# ADF7021_Transceiver.net
KiCad netlist of a schematic drawn in Altium Designer
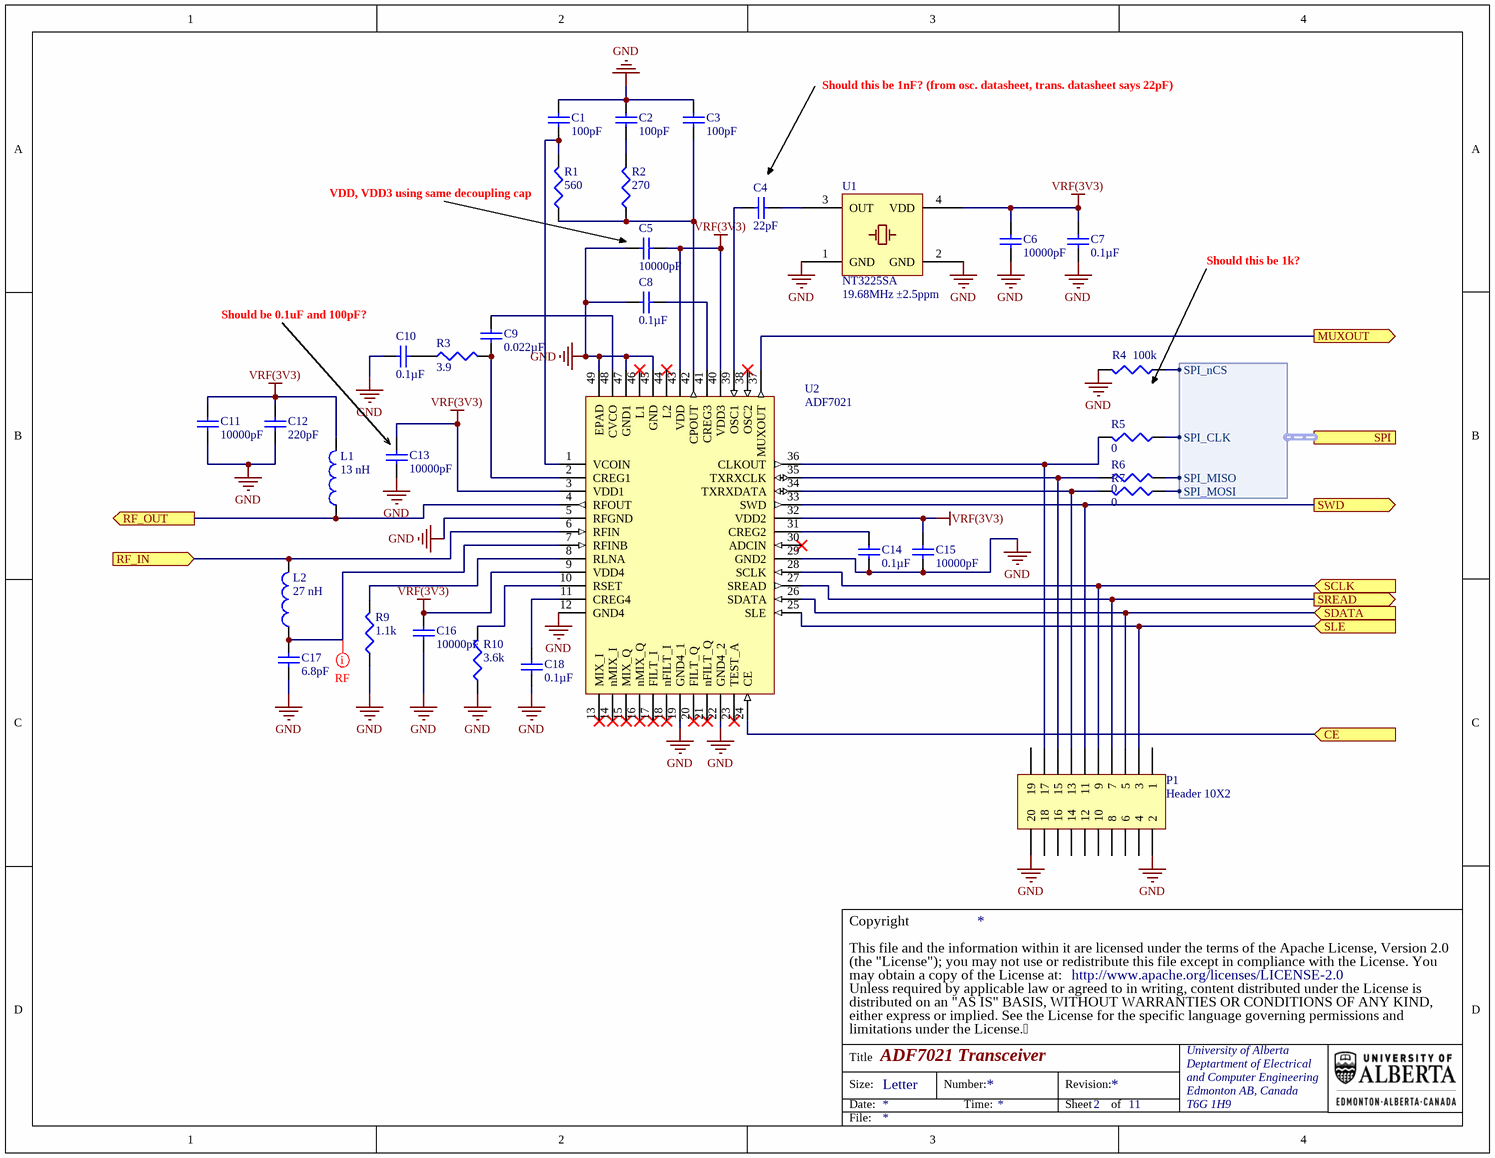
[diagram p0: ADF7021 Transceiver.SchDoc]

(export (version "E")
  (design (tool "Eeschema 10.0.6"))
  (components
    (comp (ref "C1")
      (value "100pF")
      (footprint "TDK-CGA2B")
      (description "CAP CER 100PF 100V C0G 0402")
      (fields
        (field (name "PART NUMBER") "PC-TDK-01226")
        (field (name "MANUFACTURER PART NUMBER") "CGA2B2C0G2A101J050BA")
        (field (name "PUBLISHER") "AlbertaSat")
      )
      (libsource (lib "Database") (part "Cap"))
    )
    (comp (ref "C2")
      (value "100pF")
      (footprint "TDK-CGA2B")
      (description "CAP CER 100PF 100V C0G 0402")
      (fields
        (field (name "PART NUMBER") "PC-TDK-01226")
        (field (name "MANUFACTURER PART NUMBER") "CGA2B2C0G2A101J050BA")
        (field (name "PUBLISHER") "AlbertaSat")
      )
      (libsource (lib "Database") (part "Cap"))
    )
    (comp (ref "C3")
      (value "100pF")
      (footprint "TDK-CGA2B")
      (description "CAP CER 100PF 100V C0G 0402")
      (fields
        (field (name "PART NUMBER") "PC-TDK-01226")
        (field (name "MANUFACTURER PART NUMBER") "CGA2B2C0G2A101J050BA")
        (field (name "PUBLISHER") "AlbertaSat")
      )
      (libsource (lib "Database") (part "Cap"))
    )
    (comp (ref "C4")
      (value "22pF")
      (footprint "ATC-600L")
      (description "CAP CER 22PF 200V C0G/NP0 0402")
      (fields
        (field (name "PART NUMBER") "PC-ATC-00281")
        (field (name "MANUFACTURER PART NUMBER") "600L220FT200T")
        (field (name "PUBLISHER") "AlbertaSat")
      )
      (libsource (lib "Database") (part "Cap"))
    )
    (comp (ref "C5")
      (value "10000pF")
      (footprint "TDK-CGA2B")
      (description "CAP CER 10000PF 50V X8R 0402")
      (fields
        (field (name "PART NUMBER") "PC-TDK-01877")
        (field (name "MANUFACTURER PART NUMBER") "CGA2B3X8R1H103K050BB")
        (field (name "PUBLISHER") "AlbertaSat")
      )
      (libsource (lib "Database") (part "Cap"))
    )
    (comp (ref "C6")
      (value "10000pF")
      (footprint "TDK-CGA2B")
      (description "CAP CER 10000PF 50V X8R 0402")
      (fields
        (field (name "PART NUMBER") "PC-TDK-01877")
        (field (name "MANUFACTURER PART NUMBER") "CGA2B3X8R1H103K050BB")
        (field (name "PUBLISHER") "AlbertaSat")
      )
      (libsource (lib "Database") (part "Cap"))
    )
    (comp (ref "C7")
      (value "0.1µF")
      (footprint "TDK-CGA2B")
      (description "CAP CER 0.1UF 50V X7R 0402")
      (fields
        (field (name "PART NUMBER") "PC-TDK-02259")
        (field (name "MANUFACTURER PART NUMBER") "CGA2B3X7R1H104K050BB")
        (field (name "PUBLISHER") "AlbertaSat")
      )
      (libsource (lib "Database") (part "Cap"))
    )
    (comp (ref "C8")
      (value "0.1µF")
      (footprint "TDK-CGA2B")
      (description "CAP CER 0.1UF 50V X7R 0402")
      (fields
        (field (name "PART NUMBER") "PC-TDK-02259")
        (field (name "MANUFACTURER PART NUMBER") "CGA2B3X7R1H104K050BB")
        (field (name "PUBLISHER") "AlbertaSat")
      )
      (libsource (lib "Database") (part "Cap"))
    )
    (comp (ref "C9")
      (value "0.022µF")
      (footprint "TDK-CGA2B")
      (description "CAP CER 0.022UF 50V X7R 0402")
      (fields
        (field (name "PART NUMBER") "PC-TDK-01998")
        (field (name "MANUFACTURER PART NUMBER") "CGA2B3X7R1H223K050BB")
        (field (name "PUBLISHER") "AlbertaSat")
      )
      (libsource (lib "Database") (part "Cap"))
    )
    (comp (ref "C10")
      (value "0.1µF")
      (footprint "TDK-CGA2B")
      (description "CAP CER 0.1UF 50V X7R 0402")
      (fields
        (field (name "PART NUMBER") "PC-TDK-02259")
        (field (name "MANUFACTURER PART NUMBER") "CGA2B3X7R1H104K050BB")
        (field (name "PUBLISHER") "AlbertaSat")
      )
      (libsource (lib "Database") (part "Cap"))
    )
    (comp (ref "C11")
      (value "10000pF")
      (footprint "TDK-CGA2B")
      (description "CAP CER 10000PF 50V X8R 0402")
      (fields
        (field (name "PART NUMBER") "PC-TDK-01877")
        (field (name "MANUFACTURER PART NUMBER") "CGA2B3X8R1H103K050BB")
        (field (name "PUBLISHER") "AlbertaSat")
      )
      (libsource (lib "Database") (part "Cap"))
    )
    (comp (ref "C12")
      (value "220pF")
      (footprint "TDK-CGA2B")
      (description "CAP CER 220PF 50V NP0 0402")
      (fields
        (field (name "PART NUMBER") "PC-TDK-01303")
        (field (name "MANUFACTURER PART NUMBER") "CGA2B2NP01H221J050BA")
        (field (name "PUBLISHER") "AlbertaSat")
      )
      (libsource (lib "Database") (part "Cap"))
    )
    (comp (ref "C13")
      (value "10000pF")
      (footprint "TDK-CGA2B")
      (description "CAP CER 10000PF 50V X8R 0402")
      (fields
        (field (name "PART NUMBER") "PC-TDK-01877")
        (field (name "MANUFACTURER PART NUMBER") "CGA2B3X8R1H103K050BB")
        (field (name "PUBLISHER") "AlbertaSat")
      )
      (libsource (lib "Database") (part "Cap"))
    )
    (comp (ref "C14")
      (value "0.1µF")
      (footprint "TDK-CGA2B")
      (description "CAP CER 0.1UF 50V X7R 0402")
      (fields
        (field (name "PART NUMBER") "PC-TDK-02259")
        (field (name "MANUFACTURER PART NUMBER") "CGA2B3X7R1H104K050BB")
        (field (name "PUBLISHER") "AlbertaSat")
      )
      (libsource (lib "Database") (part "Cap"))
    )
    (comp (ref "C15")
      (value "10000pF")
      (footprint "TDK-CGA2B")
      (description "CAP CER 10000PF 50V X8R 0402")
      (fields
        (field (name "PART NUMBER") "PC-TDK-01877")
        (field (name "MANUFACTURER PART NUMBER") "CGA2B3X8R1H103K050BB")
        (field (name "PUBLISHER") "AlbertaSat")
      )
      (libsource (lib "Database") (part "Cap"))
    )
    (comp (ref "C16")
      (value "10000pF")
      (footprint "TDK-CGA2B")
      (description "CAP CER 10000PF 50V X8R 0402")
      (fields
        (field (name "PART NUMBER") "PC-TDK-01877")
        (field (name "MANUFACTURER PART NUMBER") "CGA2B3X8R1H103K050BB")
        (field (name "PUBLISHER") "AlbertaSat")
      )
      (libsource (lib "Database") (part "Cap"))
    )
    (comp (ref "C17")
      (value "6.8pF")
      (footprint "ATC-600L")
      (description "CAP CER 6.8PF 200V C0G/NP0 0402")
      (fields
        (field (name "PART NUMBER") "PC-ATC-00200")
        (field (name "MANUFACTURER PART NUMBER") "600L6R8BT200T")
        (field (name "PUBLISHER") "AlbertaSat")
      )
      (libsource (lib "Database") (part "Cap"))
    )
    (comp (ref "C18")
      (value "0.1µF")
      (footprint "TDK-CGA2B")
      (description "CAP CER 0.1UF 50V X7R 0402")
      (fields
        (field (name "PART NUMBER") "PC-TDK-02259")
        (field (name "MANUFACTURER PART NUMBER") "CGA2B3X7R1H104K050BB")
        (field (name "PUBLISHER") "AlbertaSat")
      )
      (libsource (lib "Database") (part "Cap"))
    )
    (comp (ref "L1")
      (value "13 nH")
      (footprint "CCI-0402CS")
      (description "Fixed Inductors 0402CS AEC-Q200 13 nH 5 % 0.44 A")
      (fields
        (field (name "PART NUMBER") "PL-CCI-00008")
        (field (name "MANUFACTURER PART NUMBER") "0402CS-13NXJLU")
        (field (name "PUBLISHER") "AlbertaSat")
      )
      (libsource (lib "Database") (part "Inductor"))
    )
    (comp (ref "L2")
      (value "27 nH")
      (footprint "CCI-0402CS")
      (fields
        (field (name "PART NUMBER") "PL-CCI-00009")
        (field (name "MANUFACTURER PART NUMBER") "0402CS-27NXJLU")
        (field (name "PUBLISHER") "AlbertaSat")
      )
      (libsource (lib "Database") (part "Inductor"))
    )
    (comp (ref "P1")
      (value "Header 10X2")
      (footprint "MOLX-0555600207")
      (description "CONN PLUG 20POS 1.5MM SMD .5MM")
      (fields
        (field (name "PART NUMBER") "50")
        (field (name "MANUFACTURER PART NUMBER") "0555600207")
        (field (name "PUBLISHER") "Altium Limited")
      )
      (libsource (lib "Database") (part "Header 10X2"))
    )
    (comp (ref "R1")
      (value "560")
      (footprint "PANA-ERA2A")
      (description "RES SMD 560 OHM 0.1% 1/16W 0402")
      (fields
        (field (name "PART NUMBER") "15042")
        (field (name "MANUFACTURER PART NUMBER") "ERA-2ARB561X")
        (field (name "PUBLISHER") "Altium Limited")
      )
      (libsource (lib "Database") (part "Res3"))
    )
    (comp (ref "R2")
      (value "270")
      (footprint "PANA-ERA2A")
      (description "RES SMD 270 OHM 0.1% 1/16W 0402")
      (fields
        (field (name "PART NUMBER") "14593")
        (field (name "MANUFACTURER PART NUMBER") "ERA-2ARB271X")
        (field (name "PUBLISHER") "Altium Limited")
      )
      (libsource (lib "Database") (part "Res3"))
    )
    (comp (ref "R3")
      (value "3.9")
      (footprint "VSH-CRCW0402")
      (description "RES SMD 3.9 OHM 1% 1/16W 0402")
      (fields
        (field (name "PART NUMBER") "PR-VSH-00269")
        (field (name "MANUFACTURER PART NUMBER") "CRCW04023R90FKED")
        (field (name "PUBLISHER") "AlbertaSat")
      )
      (libsource (lib "Database") (part "Res3"))
    )
    (comp (ref "R4")
      (value "100k")
      (footprint "PANA-ERJ2R")
      (description "RES SMD 100K OHM 1% 1/10W 0402")
      (fields
        (field (name "PART NUMBER") "18739")
        (field (name "MANUFACTURER PART NUMBER") "ERJ-2RKF1003X")
        (field (name "PUBLISHER") "Altium Limited")
      )
      (libsource (lib "Database") (part "Res3"))
    )
    (comp (ref "R5")
      (value "0")
      (footprint "PANA-ERJ2G")
      (description "RES SMD 0.0OHM JUMPER 1/10W 0402")
      (fields (field (name "PART NUMBER") "13127") (field (name "MANUFACTURER PART NUMBER") "ERJ-2GE0R00X"))
      (libsource (lib "Database") (part "Jumper3"))
    )
    (comp (ref "R6")
      (value "0")
      (footprint "PANA-ERJ2G")
      (description "RES SMD 0.0OHM JUMPER 1/10W 0402")
      (fields (field (name "PART NUMBER") "13127") (field (name "MANUFACTURER PART NUMBER") "ERJ-2GE0R00X"))
      (libsource (lib "Database") (part "Jumper3"))
    )
    (comp (ref "R7")
      (value "0")
      (footprint "PANA-ERJ2G")
      (description "RES SMD 0.0OHM JUMPER 1/10W 0402")
      (fields (field (name "PART NUMBER") "13127") (field (name "MANUFACTURER PART NUMBER") "ERJ-2GE0R00X"))
      (libsource (lib "Database") (part "Jumper3"))
    )
    (comp (ref "R9")
      (value "1.1k")
      (footprint "PANA-ERA2A")
      (description "RES SMD 1.1K OHM 0.1% 1/16W 0402")
      (fields
        (field (name "PART NUMBER") "15460")
        (field (name "MANUFACTURER PART NUMBER") "ERA-2ARB112X")
        (field (name "PUBLISHER") "Altium Limited")
      )
      (libsource (lib "Database") (part "Res3"))
    )
    (comp (ref "R10")
      (value "3.6k")
      (footprint "PANA-ERA2A")
      (description "RES SMD 3.6K OHM 0.1% 1/16W 0402")
      (fields
        (field (name "PART NUMBER") "16432")
        (field (name "MANUFACTURER PART NUMBER") "ERA-2ARB362X")
        (field (name "PUBLISHER") "Altium Limited")
      )
      (libsource (lib "Database") (part "Res3"))
    )
    (comp (ref "U1")
      (value "NT3225SA")
      (footprint "NDK-NT3225SA")
      (description "OSC VCTCXO 19.68MHZ SMD")
      (fields
        (field (name "PART NUMBER") "PU-NDK-00001")
        (field (name "MANUFACTURER PART NUMBER") "NT3225SA-19.680000MHZ")
        (field (name "ALTIUM_VALUE") "19.68MHz")
        (field (name "FREQUENCY STABILITY") "±2.5ppm")
        (field (name "PUBLISHER") "AlbertaSat")
      )
      (libsource (lib "Database") (part "NT3225SA"))
    )
    (comp (ref "U2")
      (value "ADF7021")
      (footprint "ADI-CP-48-5")
      (description "IC RF TXRX ISM<1GHZ 48-VFQFN")
      (fields
        (field (name "RS PART NUMBER") "6977565")
        (field (name "MANUFACTURER_PART_NUMBER") "ADF7021BCPZ")
        (field (name "PUBLISHER") "AlbertaSat")
      )
      (libsource (lib "Database") (part "ADF7021BCPZ"))
    )
  )
  (nets
    (net (code "2") (name "/CE") (class "Default")
      (node (ref "U2") (pin "24") (pinfunction "CE_24") (pintype "input"))
    )
    (net (code "3") (name "/MUXOUT") (class "Default")
      (node (ref "U2") (pin "37") (pinfunction "MUXOUT_37") (pintype "output"))
    )
    (net (code "4") (name "/RF_IN") (class "Default")
      (node (ref "L2") (pin "2") (pinfunction "2_2") (pintype "passive"))
      (node (ref "U2") (pin "6") (pinfunction "RFIN_6") (pintype "input"))
    )
    (net (code "5") (name "/RF_OUT") (class "Default")
      (node (ref "L1") (pin "1") (pinfunction "1_1") (pintype "passive"))
      (node (ref "U2") (pin "4") (pinfunction "RFOUT_4") (pintype "output"))
    )
    (net (code "6") (name "/SCLK") (class "Default")
      (node (ref "P1") (pin "9") (pinfunction "9_9") (pintype "passive"))
      (node (ref "U2") (pin "28") (pinfunction "SCLK_28") (pintype "input"))
    )
    (net (code "7") (name "/SDATA") (class "Default")
      (node (ref "P1") (pin "5") (pinfunction "5_5") (pintype "passive"))
      (node (ref "U2") (pin "26") (pinfunction "SDATA_26") (pintype "input"))
    )
    (net (code "8") (name "/SLE") (class "Default")
      (node (ref "P1") (pin "3") (pinfunction "3_3") (pintype "passive"))
      (node (ref "U2") (pin "25") (pinfunction "SLE_25") (pintype "input"))
    )
    (net (code "9") (name "/SPI_CLK") (class "Default")
      (node (ref "R5") (pin "1") (pinfunction "1_1") (pintype "passive"))
    )
    (net (code "10") (name "/SPI_MISO") (class "Default")
      (node (ref "R6") (pin "2") (pinfunction "2_2") (pintype "passive"))
    )
    (net (code "11") (name "/SPI_MOSI") (class "Default")
      (node (ref "R7") (pin "1") (pinfunction "1_1") (pintype "passive"))
    )
    (net (code "12") (name "/SPI_nCS") (class "Default")
      (node (ref "R4") (pin "1") (pinfunction "1_1") (pintype "passive"))
    )
    (net (code "13") (name "/SREAD") (class "Default")
      (node (ref "P1") (pin "7") (pinfunction "7_7") (pintype "passive"))
      (node (ref "U2") (pin "27") (pinfunction "SREAD_27") (pintype "output"))
    )
    (net (code "14") (name "/SWD") (class "Default")
      (node (ref "P1") (pin "11") (pinfunction "11_11") (pintype "passive"))
      (node (ref "U2") (pin "33") (pinfunction "SWD_33") (pintype "output"))
    )
    (net (code "16") (name "GND") (class "Default")
      (node (ref "C1") (pin "2") (pinfunction "2_2") (pintype "passive"))
      (node (ref "C10") (pin "2") (pinfunction "2_2") (pintype "passive"))
      (node (ref "C11") (pin "1") (pinfunction "1_1") (pintype "passive"))
      (node (ref "C12") (pin "1") (pinfunction "1_1") (pintype "passive"))
      (node (ref "C13") (pin "1") (pinfunction "1_1") (pintype "passive"))
      (node (ref "C14") (pin "2") (pinfunction "2_2") (pintype "passive"))
      (node (ref "C15") (pin "1") (pinfunction "1_1") (pintype "passive"))
      (node (ref "C16") (pin "1") (pinfunction "1_1") (pintype "passive"))
      (node (ref "C17") (pin "1") (pinfunction "1_1") (pintype "passive"))
      (node (ref "C18") (pin "2") (pinfunction "2_2") (pintype "passive"))
      (node (ref "C2") (pin "2") (pinfunction "2_2") (pintype "passive"))
      (node (ref "C3") (pin "2") (pinfunction "2_2") (pintype "passive"))
      (node (ref "C5") (pin "1") (pinfunction "1_1") (pintype "passive"))
      (node (ref "C6") (pin "1") (pinfunction "1_1") (pintype "passive"))
      (node (ref "C7") (pin "1") (pinfunction "1_1") (pintype "passive"))
      (node (ref "C8") (pin "2") (pinfunction "2_2") (pintype "passive"))
      (node (ref "P1") (pin "2") (pinfunction "2_2") (pintype "passive"))
      (node (ref "P1") (pin "20") (pinfunction "20_20") (pintype "passive"))
      (node (ref "R10") (pin "1") (pinfunction "1_1") (pintype "passive"))
      (node (ref "R4") (pin "2") (pinfunction "2_2") (pintype "passive"))
      (node (ref "R9") (pin "1") (pinfunction "1_1") (pintype "passive"))
      (node (ref "U1") (pin "1") (pinfunction "GND_1") (pintype "passive"))
      (node (ref "U1") (pin "2") (pinfunction "GND_2") (pintype "passive"))
      (node (ref "U2") (pin "12") (pinfunction "GND4_12") (pintype "power_in"))
      (node (ref "U2") (pin "19") (pinfunction "GND4_1_19") (pintype "power_in"))
      (node (ref "U2") (pin "22") (pinfunction "GND4_2_22") (pintype "power_in"))
      (node (ref "U2") (pin "29") (pinfunction "GND2_29") (pintype "power_in"))
      (node (ref "U2") (pin "45") (pinfunction "GND_45") (pintype "power_in"))
      (node (ref "U2") (pin "47") (pinfunction "GND1_47") (pintype "power_in"))
      (node (ref "U2") (pin "49") (pinfunction "EPAD_49") (pintype "passive"))
      (node (ref "U2") (pin "5") (pinfunction "RFGND_5") (pintype "power_in"))
    )
    (net (code "17") (name "Net-(C2-Pad1)") (class "Default")
      (node (ref "C2") (pin "1") (pinfunction "1_1") (pintype "passive"))
      (node (ref "R2") (pin "2") (pinfunction "2_2") (pintype "passive"))
    )
    (net (code "18") (name "Net-(C10-Pad1)") (class "Default")
      (node (ref "C10") (pin "1") (pinfunction "1_1") (pintype "passive"))
      (node (ref "R3") (pin "1") (pinfunction "1_1") (pintype "passive"))
    )
    (net (code "19") (name "Net-(U1-OUT)") (class "Default")
      (node (ref "C4") (pin "2") (pinfunction "2_2") (pintype "passive"))
      (node (ref "U1") (pin "3") (pinfunction "OUT_3") (pintype "passive"))
    )
    (net (code "20") (name "Net-(U2-CLKOUT)") (class "Default")
      (node (ref "P1") (pin "17") (pinfunction "17_17") (pintype "passive"))
      (node (ref "R5") (pin "2") (pinfunction "2_2") (pintype "passive"))
      (node (ref "U2") (pin "36") (pinfunction "CLKOUT_36") (pintype "output"))
    )
    (net (code "21") (name "Net-(U2-CPOUT)") (class "Default")
      (node (ref "C3") (pin "1") (pinfunction "1_1") (pintype "passive"))
      (node (ref "R1") (pin "1") (pinfunction "1_1") (pintype "passive"))
      (node (ref "R2") (pin "1") (pinfunction "1_1") (pintype "passive"))
      (node (ref "U2") (pin "42") (pinfunction "CPOUT_42") (pintype "output"))
    )
    (net (code "22") (name "Net-(U2-CREG1)") (class "Default")
      (node (ref "C9") (pin "1") (pinfunction "1_1") (pintype "passive"))
      (node (ref "R3") (pin "2") (pinfunction "2_2") (pintype "passive"))
      (node (ref "U2") (pin "2") (pinfunction "CREG1_2") (pintype "passive"))
    )
    (net (code "23") (name "Net-(U2-CREG2)") (class "Default")
      (node (ref "C14") (pin "1") (pinfunction "1_1") (pintype "passive"))
      (node (ref "U2") (pin "31") (pinfunction "CREG2_31") (pintype "passive"))
    )
    (net (code "24") (name "Net-(U2-CREG3)") (class "Default")
      (node (ref "C8") (pin "1") (pinfunction "1_1") (pintype "passive"))
      (node (ref "U2") (pin "41") (pinfunction "CREG3_41") (pintype "passive"))
    )
    (net (code "25") (name "Net-(U2-CREG4)") (class "Default")
      (node (ref "C18") (pin "1") (pinfunction "1_1") (pintype "passive"))
      (node (ref "U2") (pin "11") (pinfunction "CREG4_11") (pintype "passive"))
    )
    (net (code "26") (name "Net-(U2-CVCO)") (class "Default")
      (node (ref "C9") (pin "2") (pinfunction "2_2") (pintype "passive"))
      (node (ref "U2") (pin "48") (pinfunction "CVCO_48") (pintype "passive"))
    )
    (net (code "27") (name "Net-(U2-OSC1)") (class "Default")
      (node (ref "C4") (pin "1") (pinfunction "1_1") (pintype "passive"))
      (node (ref "U2") (pin "39") (pinfunction "OSC1_39") (pintype "input"))
    )
    (net (code "28") (name "Net-(U2-RFINB)") (class "Default")
      (node (ref "C17") (pin "2") (pinfunction "2_2") (pintype "passive"))
      (node (ref "L2") (pin "1") (pinfunction "1_1") (pintype "passive"))
      (node (ref "U2") (pin "7") (pinfunction "RFINB_7") (pintype "input"))
    )
    (net (code "29") (name "Net-(U2-RLNA)") (class "Default")
      (node (ref "R9") (pin "2") (pinfunction "2_2") (pintype "passive"))
      (node (ref "U2") (pin "8") (pinfunction "RLNA_8") (pintype "passive"))
    )
    (net (code "30") (name "Net-(U2-RSET)") (class "Default")
      (node (ref "R10") (pin "2") (pinfunction "2_2") (pintype "passive"))
      (node (ref "U2") (pin "10") (pinfunction "RSET_10") (pintype "passive"))
    )
    (net (code "31") (name "Net-(U2-TXRXCLK)") (class "Default")
      (node (ref "P1") (pin "15") (pinfunction "15_15") (pintype "passive"))
      (node (ref "R6") (pin "1") (pinfunction "1_1") (pintype "passive"))
      (node (ref "U2") (pin "35") (pinfunction "TXRXCLK_35") (pintype "bidirectional"))
    )
    (net (code "32") (name "Net-(U2-TXRXDATA)") (class "Default")
      (node (ref "P1") (pin "13") (pinfunction "13_13") (pintype "passive"))
      (node (ref "R7") (pin "2") (pinfunction "2_2") (pintype "passive"))
      (node (ref "U2") (pin "34") (pinfunction "TXRXDATA_34") (pintype "bidirectional"))
    )
    (net (code "33") (name "Net-(U2-VCOIN)") (class "Default")
      (node (ref "C1") (pin "1") (pinfunction "1_1") (pintype "passive"))
      (node (ref "R1") (pin "2") (pinfunction "2_2") (pintype "passive"))
      (node (ref "U2") (pin "1") (pinfunction "VCOIN_1") (pintype "passive"))
    )
    (net (code "34") (name "VRF(3V3)") (class "Default")
      (node (ref "C11") (pin "2") (pinfunction "2_2") (pintype "passive"))
      (node (ref "C12") (pin "2") (pinfunction "2_2") (pintype "passive"))
      (node (ref "C13") (pin "2") (pinfunction "2_2") (pintype "passive"))
      (node (ref "C15") (pin "2") (pinfunction "2_2") (pintype "passive"))
      (node (ref "C16") (pin "2") (pinfunction "2_2") (pintype "passive"))
      (node (ref "C5") (pin "2") (pinfunction "2_2") (pintype "passive"))
      (node (ref "C6") (pin "2") (pinfunction "2_2") (pintype "passive"))
      (node (ref "C7") (pin "2") (pinfunction "2_2") (pintype "passive"))
      (node (ref "L1") (pin "2") (pinfunction "2_2") (pintype "passive"))
      (node (ref "U1") (pin "4") (pinfunction "VDD_4") (pintype "passive"))
      (node (ref "U2") (pin "3") (pinfunction "VDD1_3") (pintype "power_in"))
      (node (ref "U2") (pin "32") (pinfunction "VDD2_32") (pintype "power_in"))
      (node (ref "U2") (pin "40") (pinfunction "VDD3_40") (pintype "power_in"))
      (node (ref "U2") (pin "43") (pinfunction "VDD_43") (pintype "power_in"))
      (node (ref "U2") (pin "9") (pinfunction "VDD4_9") (pintype "power_in"))
    )
    (net (code "35") (name "unconnected-(P1-Pad1)") (class "Default")
      (node (ref "P1") (pin "1") (pinfunction "1_1") (pintype "passive"))
    )
    (net (code "36") (name "unconnected-(P1-Pad4)") (class "Default")
      (node (ref "P1") (pin "4") (pinfunction "4_4") (pintype "passive"))
    )
    (net (code "37") (name "unconnected-(P1-Pad6)") (class "Default")
      (node (ref "P1") (pin "6") (pinfunction "6_6") (pintype "passive"))
    )
    (net (code "38") (name "unconnected-(P1-Pad8)") (class "Default")
      (node (ref "P1") (pin "8") (pinfunction "8_8") (pintype "passive"))
    )
    (net (code "39") (name "unconnected-(P1-Pad10)") (class "Default")
      (node (ref "P1") (pin "10") (pinfunction "10_10") (pintype "passive"))
    )
    (net (code "40") (name "unconnected-(P1-Pad12)") (class "Default")
      (node (ref "P1") (pin "12") (pinfunction "12_12") (pintype "passive"))
    )
    (net (code "41") (name "unconnected-(P1-Pad14)") (class "Default")
      (node (ref "P1") (pin "14") (pinfunction "14_14") (pintype "passive"))
    )
    (net (code "42") (name "unconnected-(P1-Pad16)") (class "Default")
      (node (ref "P1") (pin "16") (pinfunction "16_16") (pintype "passive"))
    )
    (net (code "43") (name "unconnected-(P1-Pad18)") (class "Default")
      (node (ref "P1") (pin "18") (pinfunction "18_18") (pintype "passive"))
    )
    (net (code "44") (name "unconnected-(P1-Pad19)") (class "Default")
      (node (ref "P1") (pin "19") (pinfunction "19_19") (pintype "passive"))
    )
    (net (code "45") (name "unconnected-(U2-ADCIN-Pad30)") (class "Default")
      (node (ref "U2") (pin "30") (pinfunction "ADCIN_30") (pintype "input+no_connect"))
    )
    (net (code "46") (name "unconnected-(U2-FILT_I-Pad17)") (class "Default")
      (node (ref "U2") (pin "17") (pinfunction "FILT_I_17") (pintype "tri_state+no_connect"))
    )
    (net (code "47") (name "unconnected-(U2-FILT_Q-Pad20)") (class "Default")
      (node (ref "U2") (pin "20") (pinfunction "FILT_Q_20") (pintype "tri_state+no_connect"))
    )
    (net (code "48") (name "unconnected-(U2-L1-Pad46)") (class "Default")
      (node (ref "U2") (pin "46") (pinfunction "L1_46") (pintype "passive+no_connect"))
    )
    (net (code "49") (name "unconnected-(U2-L2-Pad44)") (class "Default")
      (node (ref "U2") (pin "44") (pinfunction "L2_44") (pintype "passive+no_connect"))
    )
    (net (code "50") (name "unconnected-(U2-MIX_I-Pad13)") (class "Default")
      (node (ref "U2") (pin "13") (pinfunction "MIX_I_13") (pintype "tri_state+no_connect"))
    )
    (net (code "51") (name "unconnected-(U2-MIX_Q-Pad15)") (class "Default")
      (node (ref "U2") (pin "15") (pinfunction "MIX_Q_15") (pintype "tri_state+no_connect"))
    )
    (net (code "52") (name "unconnected-(U2-OSC2-Pad38)") (class "Default")
      (node (ref "U2") (pin "38") (pinfunction "OSC2_38") (pintype "input+no_connect"))
    )
    (net (code "53") (name "unconnected-(U2-TEST_A-Pad23)") (class "Default")
      (node (ref "U2") (pin "23") (pinfunction "TEST_A_23") (pintype "tri_state+no_connect"))
    )
    (net (code "54") (name "unconnected-(U2-nFILT_I-Pad18)") (class "Default")
      (node (ref "U2") (pin "18") (pinfunction "nFILT_I_18") (pintype "tri_state+no_connect"))
    )
    (net (code "55") (name "unconnected-(U2-nFILT_Q-Pad21)") (class "Default")
      (node (ref "U2") (pin "21") (pinfunction "nFILT_Q_21") (pintype "tri_state+no_connect"))
    )
    (net (code "56") (name "unconnected-(U2-nMIX_I-Pad14)") (class "Default")
      (node (ref "U2") (pin "14") (pinfunction "nMIX_I_14") (pintype "tri_state+no_connect"))
    )
    (net (code "57") (name "unconnected-(U2-nMIX_Q-Pad16)") (class "Default")
      (node (ref "U2") (pin "16") (pinfunction "nMIX_Q_16") (pintype "tri_state+no_connect"))
    )
  )
)
